# Power.net
KiCad netlist of a schematic drawn in Altium Designer
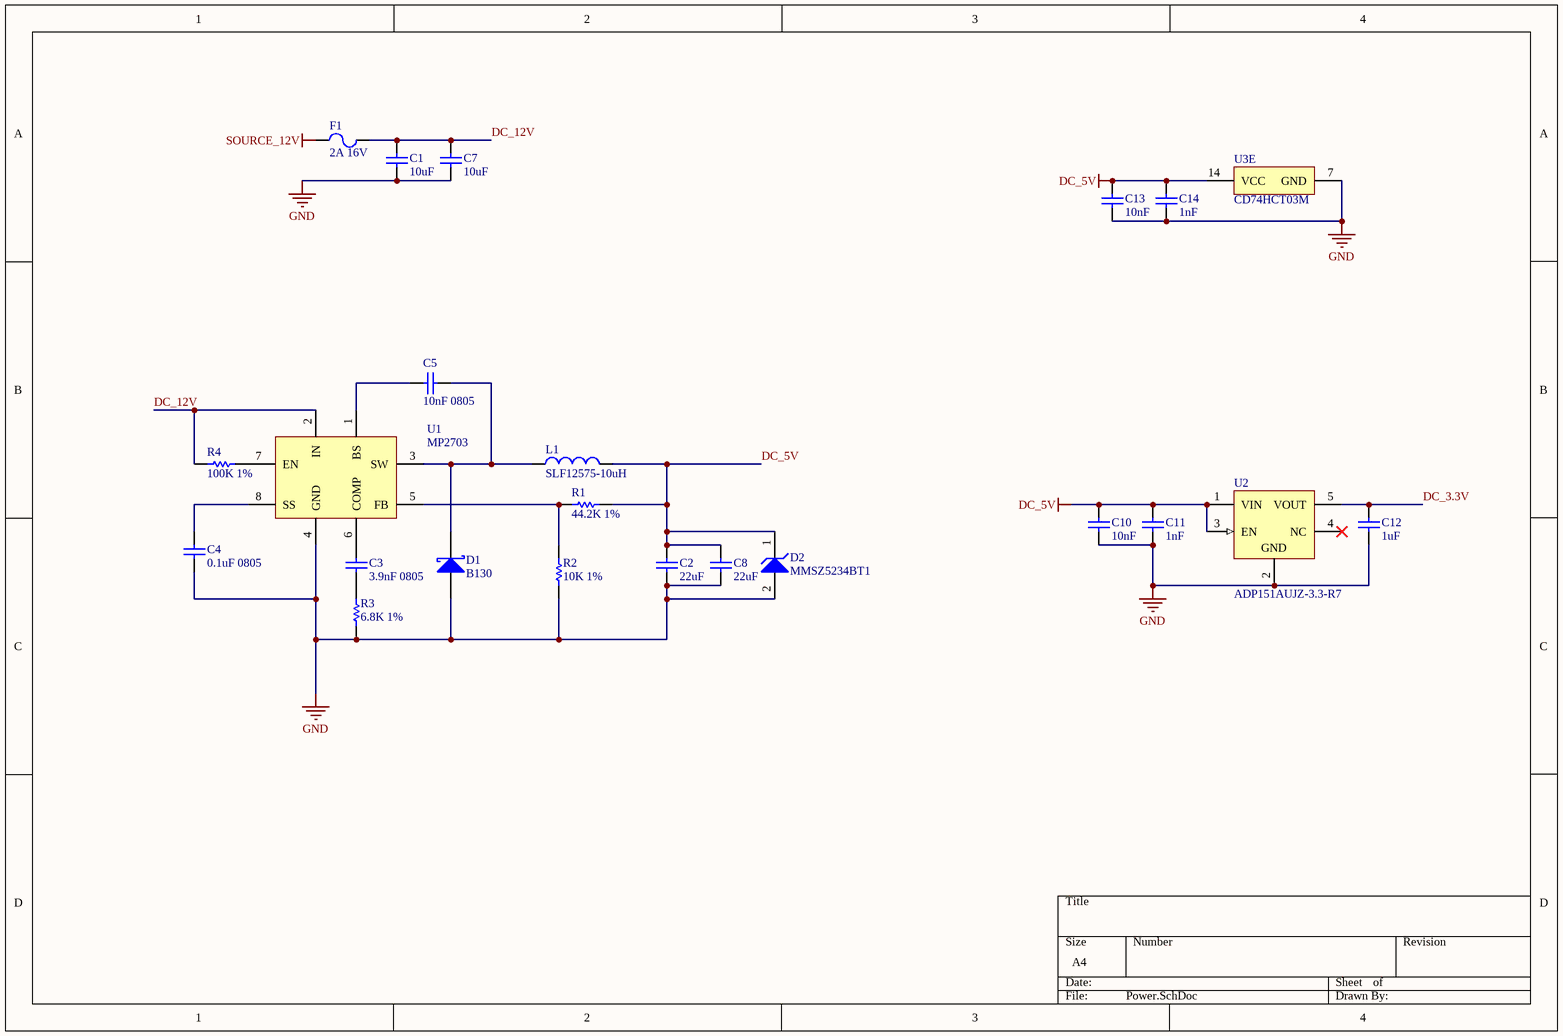
[diagram p0: Power.SchDoc]

(export (version "E")
  (design (tool "Eeschema 10.0.6"))
  (components
    (comp (ref "C1")
      (value "10uF")
      (footprint "CAPC1206(3216)190_L")
      (description "CAP 10uF 25V ±10% 1206 (3216 Metric) Thickness 1.9mm SMD")
      (fields (field (name "TOLERANCE") "Â±10%"))
      (libsource (lib "Altium Content Vault") (part "CMP-1037-04979-1"))
    )
    (comp (ref "C2")
      (value "22uF")
      (footprint "CAPC1210(3225)250_M")
      (description "CAP 22uF 10V ±10% 1210 (3225 Metric) Thickness 2.5mm SMD")
      (fields (field (name "TOLERANCE") "Â±10%"))
      (libsource (lib "Altium Content Vault") (part "CMP-1038-02267-1"))
    )
    (comp (ref "C3")
      (value "3.9nF 0805")
      (footprint "CAPC0805(2012)145_N")
      (description "CAP 3.9uF 10V ±10% 0805 (2012 Metric) Thickness 1.45mm SMD")
      (fields (field (name "TOLERANCE") "Â±10%"))
      (libsource (lib "Altium Content Vault") (part "CMP-1036-04874-1"))
    )
    (comp (ref "C4")
      (value "0.1uF 0805")
      (footprint "CAPC0805(2012)145_N")
      (description "CAP 3.9uF 10V ±10% 0805 (2012 Metric) Thickness 1.45mm SMD")
      (fields (field (name "TOLERANCE") "Â±10%"))
      (libsource (lib "Altium Content Vault") (part "CMP-1036-04874-1"))
    )
    (comp (ref "C5")
      (value "10nF 0805")
      (footprint "CAPC0805(2012)145_N")
      (description "CAP 3.9uF 10V ±10% 0805 (2012 Metric) Thickness 1.45mm SMD")
      (fields (field (name "TOLERANCE") "Â±10%"))
      (libsource (lib "Altium Content Vault") (part "CMP-1036-04874-1"))
    )
    (comp (ref "C7")
      (value "10uF")
      (footprint "CAPC1206(3216)190_L")
      (description "CAP 10uF 25V ±10% 1206 (3216 Metric) Thickness 1.9mm SMD")
      (fields (field (name "TOLERANCE") "Â±10%"))
      (libsource (lib "Altium Content Vault") (part "CMP-1037-04979-1"))
    )
    (comp (ref "C8")
      (value "22uF")
      (footprint "CAPC1210(3225)250_M")
      (description "CAP 22uF 10V ±10% 1210 (3225 Metric) Thickness 2.5mm SMD")
      (fields (field (name "TOLERANCE") "Â±10%"))
      (libsource (lib "Altium Content Vault") (part "CMP-1038-02267-1"))
    )
    (comp (ref "C10")
      (value "10nF")
      (footprint "CAPC0805(2012)100_N")
      (description "CAP 10nF 16V ±10% 0805 (2012 Metric) Thickness 1mm SMD")
      (fields (field (name "TOLERANCE") "Â±10%"))
      (libsource (lib "Altium Content Vault") (part "CMP-1036-03820-1"))
    )
    (comp (ref "C11")
      (value "1nF")
      (footprint "CAPC0805(2012)100_N")
      (description "CAP 10nF 16V ±10% 0805 (2012 Metric) Thickness 1mm SMD")
      (fields (field (name "TOLERANCE") "Â±10%"))
      (libsource (lib "Altium Content Vault") (part "CMP-1036-03820-1"))
    )
    (comp (ref "C12")
      (value "1uF")
      (footprint "CAPC0805(2012)100_L")
      (description "CAP 10nF 16V ±10% 0805 (2012 Metric) Thickness 1mm SMD")
      (fields (field (name "TOLERANCE") "Â±10%"))
      (libsource (lib "Altium Content Vault") (part "CMP-1036-03820-1"))
    )
    (comp (ref "C13")
      (value "10nF")
      (footprint "CAPC0805(2012)100_N")
      (description "CAP 10nF 16V ±10% 0805 (2012 Metric) Thickness 1mm SMD")
      (fields (field (name "TOLERANCE") "Â±10%"))
      (libsource (lib "Altium Content Vault") (part "CMP-1036-03820-1"))
    )
    (comp (ref "C14")
      (value "1nF")
      (footprint "CAPC0805(2012)100_N")
      (description "CAP 10nF 16V ±10% 0805 (2012 Metric) Thickness 1mm SMD")
      (fields (field (name "TOLERANCE") "Â±10%"))
      (libsource (lib "Altium Content Vault") (part "CMP-1036-03820-1"))
    )
    (comp (ref "D1")
      (value "B130")
      (footprint "DIOD-SOD-123-2-A_V")
      (description "Schottky Barrier Rectifier, 30 V, 1 A, -55 to 125 degC, 2-Pin SMD, RoHS, Tape and Reel")
      (fields (field (name "MANUFACTURER") "DiodesIncorporated"))
      (libsource (lib "Altium Content Vault") (part "CMP-2000-05884-1"))
    )
    (comp (ref "D2")
      (value "MMSZ5234BT1")
      (footprint "ONSC-SOD-123-2-425-04_V")
      (description "Zener Voltage Regulator, 500 mW, 2-Pin SOD-123, Tape and Reel")
      (fields (field (name "MANUFACTURER") "On Semiconductor"))
      (libsource (lib "Altium Content Vault") (part "CMP-1060-00360-1"))
    )
    (comp (ref "F1")
      (value "2A 16V")
      (footprint "LFUS-1812L16012_V")
      (description "POLY-FUSE(R) Resettable PTC, 1.6 A, -40 to 85 degC, 1812 (4532 Metric), RoHS, Tape and Reel")
      (fields (field (name "TOLERANCE") "10%"))
      (libsource (lib "Altium Content Vault") (part "CMP-1700-00005-1"))
    )
    (comp (ref "L1")
      (value "SLF12575-10uH")
      (footprint "TDK-SLF12575-H_V")
      (description "Power Inductor, 33 uH, +/-20%, -40 to 125 degC,2-Pin SMD, RoHS, Tape and Reel")
      (fields (field (name "MANUFACTURER") "TDK"))
      (libsource (lib "Altium Content Vault") (part "CMP-1663-00003-4"))
    )
    (comp (ref "R1")
      (value "44.2K 1%")
      (footprint "RESC0805(2012)_L")
      (fields (field (name "TOLERANCE") "1 %") (field (name "POWER") "0.125 W"))
      (libsource (lib "Altium Content Vault") (part "CMP-1013-00736-1"))
    )
    (comp (ref "R2")
      (value "10K 1%")
      (footprint "RESC0805(2012)_L")
      (fields (field (name "TOLERANCE") "1 %") (field (name "POWER") "0.125 W"))
      (libsource (lib "Altium Content Vault") (part "CMP-1013-00736-1"))
    )
    (comp (ref "R3")
      (value "6.8K 1%")
      (footprint "RESC0805(2012)_L")
      (fields (field (name "TOLERANCE") "1 %") (field (name "POWER") "0.125 W"))
      (libsource (lib "Altium Content Vault") (part "CMP-1013-00736-1"))
    )
    (comp (ref "R4")
      (value "100K 1%")
      (footprint "RESC0805(2012)_L")
      (fields (field (name "TOLERANCE") "1 %") (field (name "POWER") "0.125 W"))
      (libsource (lib "Altium Content Vault") (part "CMP-1013-00736-1"))
    )
    (comp (ref "U1")
      (value "MP2703")
      (footprint "LC-SOP-8_EP_150mil")
      (description "MP2307 – 3A, 23V, 340KHz SYNCHRONOUS RECTIFIED STEP-DOWN CONVERTER")
      (libsource (lib "Common") (part "MP2307"))
    )
    (comp (ref "U2")
      (value "ADP151AUJZ-3.3-R7")
      (footprint "ADI-UJ-5_M")
      (fields (field (name "MANUFACTURER") "Analog Devices"))
      (libsource (lib "Altium Content Vault") (part "CMP-0786-00387-1"))
    )
    (comp (ref "U3")
      (value "CD74HCT03M")
      (footprint "D0014A_L")
      (description "High Speed CMOS Logic Quad 2-Input NAND Gates with Open Drain, D0014A, TUBE")
      (fields
        (field (name "MANUFACTURER") "Texas Instruments")
        (field (name "GENERIC PART NUMBER") "CD74HCT03")
      )
      (libsource (lib "Altium Content Vault") (part "CMP-1627-00022-2"))
    )
  )
  (nets
    (net (code "1") (name "/DC_3.3V") (class "Default")
      (node (ref "C12") (pin "2") (pinfunction "2_2") (pintype "passive"))
      (node (ref "U2") (pin "5") (pinfunction "VOUT_5") (pintype "power_in"))
    )
    (net (code "2") (name "/DC_12V") (class "Default")
      (node (ref "C1") (pin "2") (pinfunction "2_2") (pintype "passive"))
      (node (ref "C7") (pin "2") (pinfunction "2_2") (pintype "passive"))
      (node (ref "F1") (pin "2") (pinfunction "2_2") (pintype "passive"))
      (node (ref "R4") (pin "1") (pinfunction "1_1") (pintype "passive"))
      (node (ref "U1") (pin "2") (pinfunction "IN_2") (pintype "passive"))
    )
    (net (code "3") (name "DC_5V") (class "Default")
      (node (ref "C10") (pin "2") (pinfunction "2_2") (pintype "passive"))
      (node (ref "C11") (pin "2") (pinfunction "2_2") (pintype "passive"))
      (node (ref "C13") (pin "2") (pinfunction "2_2") (pintype "passive"))
      (node (ref "C14") (pin "2") (pinfunction "2_2") (pintype "passive"))
      (node (ref "C2") (pin "2") (pinfunction "2_2") (pintype "passive"))
      (node (ref "C8") (pin "2") (pinfunction "2_2") (pintype "passive"))
      (node (ref "D2") (pin "1") (pinfunction "K_1") (pintype "passive"))
      (node (ref "L1") (pin "2") (pinfunction "2_2") (pintype "passive"))
      (node (ref "R1") (pin "1") (pinfunction "1_1") (pintype "passive"))
      (node (ref "U2") (pin "1") (pinfunction "VIN_1") (pintype "power_in"))
      (node (ref "U2") (pin "3") (pinfunction "EN_3") (pintype "input"))
      (node (ref "U3") (pin "14") (pinfunction "VCC_14") (pintype "power_in"))
    )
    (net (code "4") (name "GND") (class "Default")
      (node (ref "C1") (pin "1") (pinfunction "1_1") (pintype "passive"))
      (node (ref "C10") (pin "1") (pinfunction "1_1") (pintype "passive"))
      (node (ref "C11") (pin "1") (pinfunction "1_1") (pintype "passive"))
      (node (ref "C12") (pin "1") (pinfunction "1_1") (pintype "passive"))
      (node (ref "C13") (pin "1") (pinfunction "1_1") (pintype "passive"))
      (node (ref "C14") (pin "1") (pinfunction "1_1") (pintype "passive"))
      (node (ref "C2") (pin "1") (pinfunction "1_1") (pintype "passive"))
      (node (ref "C4") (pin "1") (pinfunction "1_1") (pintype "passive"))
      (node (ref "C7") (pin "1") (pinfunction "1_1") (pintype "passive"))
      (node (ref "C8") (pin "1") (pinfunction "1_1") (pintype "passive"))
      (node (ref "D1") (pin "1") (pinfunction "A_1") (pintype "passive"))
      (node (ref "D2") (pin "2") (pinfunction "A_2") (pintype "passive"))
      (node (ref "R2") (pin "1") (pinfunction "1_1") (pintype "passive"))
      (node (ref "R3") (pin "1") (pinfunction "1_1") (pintype "passive"))
      (node (ref "U1") (pin "4") (pinfunction "GND_4") (pintype "passive"))
      (node (ref "U2") (pin "2") (pinfunction "GND_2") (pintype "power_in"))
      (node (ref "U3") (pin "7") (pinfunction "GND_7") (pintype "power_in"))
    )
    (net (code "5") (name "Net-(C3-Pad1)") (class "Default")
      (node (ref "C3") (pin "1") (pinfunction "1_1") (pintype "passive"))
      (node (ref "R3") (pin "2") (pinfunction "2_2") (pintype "passive"))
    )
    (net (code "6") (name "Net-(D1-K)") (class "Default")
      (node (ref "C5") (pin "1") (pinfunction "1_1") (pintype "passive"))
      (node (ref "D1") (pin "2") (pinfunction "K_2") (pintype "passive"))
      (node (ref "L1") (pin "1") (pinfunction "1_1") (pintype "passive"))
      (node (ref "U1") (pin "3") (pinfunction "SW_3") (pintype "passive"))
    )
    (net (code "7") (name "Net-(U1-BS)") (class "Default")
      (node (ref "C5") (pin "2") (pinfunction "2_2") (pintype "passive"))
      (node (ref "U1") (pin "1") (pinfunction "BS_1") (pintype "passive"))
    )
    (net (code "8") (name "Net-(U1-COMP)") (class "Default")
      (node (ref "C3") (pin "2") (pinfunction "2_2") (pintype "passive"))
      (node (ref "U1") (pin "6") (pinfunction "COMP_6") (pintype "passive"))
    )
    (net (code "9") (name "Net-(U1-EN)") (class "Default")
      (node (ref "R4") (pin "2") (pinfunction "2_2") (pintype "passive"))
      (node (ref "U1") (pin "7") (pinfunction "EN_7") (pintype "passive"))
    )
    (net (code "10") (name "Net-(U1-FB)") (class "Default")
      (node (ref "R1") (pin "2") (pinfunction "2_2") (pintype "passive"))
      (node (ref "R2") (pin "2") (pinfunction "2_2") (pintype "passive"))
      (node (ref "U1") (pin "5") (pinfunction "FB_5") (pintype "passive"))
    )
    (net (code "11") (name "Net-(U1-SS)") (class "Default")
      (node (ref "C4") (pin "2") (pinfunction "2_2") (pintype "passive"))
      (node (ref "U1") (pin "8") (pinfunction "SS_8") (pintype "passive"))
    )
    (net (code "12") (name "SOURCE_12V") (class "Default")
      (node (ref "F1") (pin "1") (pinfunction "1_1") (pintype "passive"))
    )
    (net (code "13") (name "unconnected-(U2-NC-Pad4)") (class "Default")
      (node (ref "U2") (pin "4") (pinfunction "NC_4") (pintype "passive+no_connect"))
    )
  )
)
